# Adafruit_PB86_Breakout.net
KiCad netlist of a schematic drawn in EAGLE
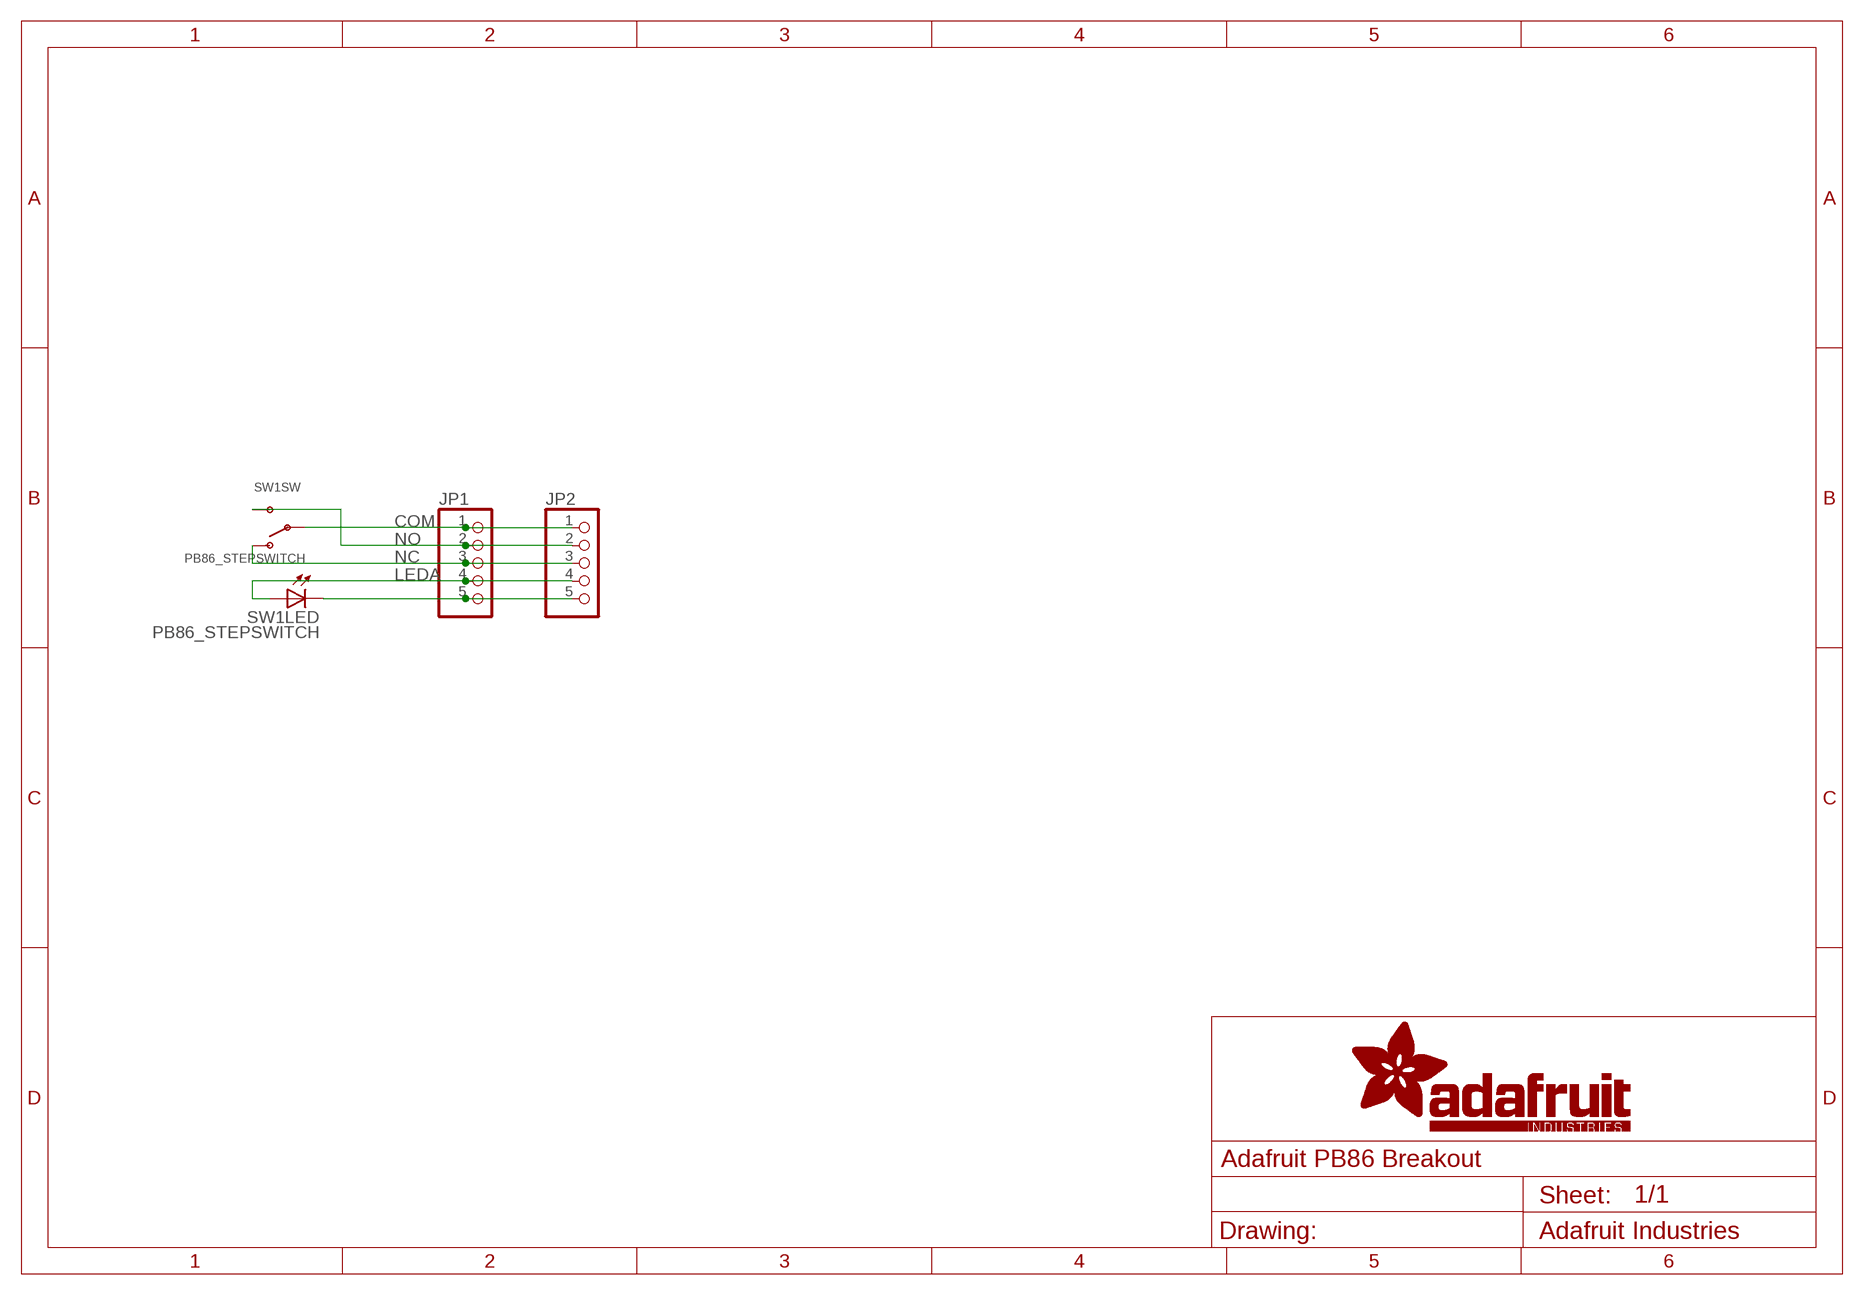
[diagram p0: schematic, sheet 1]

(export (version "E")
  (design (tool "Eeschema 10.0.6"))
  (components
    (comp (ref "JP1")
      (value "HEADER-1X5ROUND")
      (footprint "eagle-import:1X05_ROUND")
      (libsource (lib "eagle-import") (part "HEADER-1X5ROUND"))
    )
    (comp (ref "JP2")
      (value "HEADER-1X5ROUND")
      (footprint "eagle-import:1X05_ROUND")
      (libsource (lib "eagle-import") (part "HEADER-1X5ROUND"))
    )
    (comp (ref "SW1")
      (value "PB86_STEPSWITCH")
      (footprint "eagle-import:PB86")
      (libsource (lib "eagle-import") (part "PB86_STEPSWITCH"))
    )
  )
  (nets
    (net (code "1") (name "/COM") (class "Default")
      (node (ref "JP1") (pin "1") (pinfunction "1_1") (pintype "passive"))
      (node (ref "JP2") (pin "1") (pinfunction "1_1") (pintype "passive"))
      (node (ref "SW1") (pin "1A") (pinfunction "P_1A") (pintype "passive"))
      (node (ref "SW1") (pin "1B") (pinfunction "P_1B") (pintype "passive"))
    )
    (net (code "2") (name "/LEDA") (class "Default")
      (node (ref "JP1") (pin "4") (pinfunction "4_4") (pintype "passive"))
      (node (ref "JP2") (pin "4") (pinfunction "4_4") (pintype "passive"))
      (node (ref "SW1") (pin "LED+") (pinfunction "A_LED+") (pintype "passive"))
    )
    (net (code "3") (name "/NC") (class "Default")
      (node (ref "JP1") (pin "3") (pinfunction "3_3") (pintype "passive"))
      (node (ref "JP2") (pin "3") (pinfunction "3_3") (pintype "passive"))
      (node (ref "SW1") (pin "3") (pinfunction "O_3") (pintype "passive"))
    )
    (net (code "4") (name "/NO") (class "Default")
      (node (ref "JP1") (pin "2") (pinfunction "2_2") (pintype "passive"))
      (node (ref "JP2") (pin "2") (pinfunction "2_2") (pintype "passive"))
      (node (ref "SW1") (pin "2") (pinfunction "S_2") (pintype "passive"))
    )
    (net (code "5") (name "Net-(SW1A-C)") (class "Default")
      (node (ref "JP1") (pin "5") (pinfunction "5_5") (pintype "passive"))
      (node (ref "JP2") (pin "5") (pinfunction "5_5") (pintype "passive"))
      (node (ref "SW1") (pin "LED-") (pinfunction "C_LED-") (pintype "passive"))
    )
  )
)
